# espMDL_dht11_1B.net
KiCad netlist of a schematic drawn in EAGLE
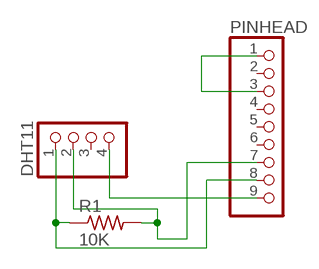
[diagram p0: schematic, sheet 1]

(export (version "E")
  (design (tool "Eeschema 10.0.6"))
  (components
    (comp (ref "DHT11")
      (value "PINHD-1X4")
      (footprint "eagle-import:1X04")
      (libsource (lib "eagle-import") (part "PINHD-1X4"))
    )
    (comp (ref "PINHEAD")
      (value "PINHD-1X9")
      (footprint "eagle-import:1X09")
      (libsource (lib "eagle-import") (part "PINHD-1X9"))
    )
    (comp (ref "R1")
      (value "10K")
      (footprint "eagle-import:0204_7")
      (libsource (lib "eagle-import") (part "R-US_0204/7"))
    )
  )
  (nets
    (net (code "1") (name "Net-(DHT11-Pad1)") (class "Default")
      (node (ref "DHT11") (pin "1") (pinfunction "1_1") (pintype "passive"))
      (node (ref "PINHEAD") (pin "8") (pinfunction "8_8") (pintype "passive"))
      (node (ref "R1") (pin "1") (pinfunction "1_1") (pintype "passive"))
    )
    (net (code "2") (name "Net-(DHT11-Pad2)") (class "Default")
      (node (ref "DHT11") (pin "2") (pinfunction "2_2") (pintype "passive"))
      (node (ref "PINHEAD") (pin "7") (pinfunction "7_7") (pintype "passive"))
      (node (ref "R1") (pin "2") (pinfunction "2_2") (pintype "passive"))
    )
    (net (code "3") (name "Net-(DHT11-Pad4)") (class "Default")
      (node (ref "DHT11") (pin "4") (pinfunction "4_4") (pintype "passive"))
      (node (ref "PINHEAD") (pin "9") (pinfunction "9_9") (pintype "passive"))
    )
    (net (code "4") (name "Net-(PINHEAD-Pad1)") (class "Default")
      (node (ref "PINHEAD") (pin "1") (pinfunction "1_1") (pintype "passive"))
      (node (ref "PINHEAD") (pin "3") (pinfunction "3_3") (pintype "passive"))
    )
    (net (code "5") (name "unconnected-(DHT11-Pad3)") (class "Default")
      (node (ref "DHT11") (pin "3") (pinfunction "3_3") (pintype "passive"))
    )
    (net (code "6") (name "unconnected-(PINHEAD-Pad2)") (class "Default")
      (node (ref "PINHEAD") (pin "2") (pinfunction "2_2") (pintype "passive"))
    )
    (net (code "7") (name "unconnected-(PINHEAD-Pad4)") (class "Default")
      (node (ref "PINHEAD") (pin "4") (pinfunction "4_4") (pintype "passive"))
    )
    (net (code "8") (name "unconnected-(PINHEAD-Pad5)") (class "Default")
      (node (ref "PINHEAD") (pin "5") (pinfunction "5_5") (pintype "passive"))
    )
    (net (code "9") (name "unconnected-(PINHEAD-Pad6)") (class "Default")
      (node (ref "PINHEAD") (pin "6") (pinfunction "6_6") (pintype "passive"))
    )
  )
)
